# pca20020_sheet7_sound_and_light.net
KiCad netlist of a schematic drawn in Altium Designer
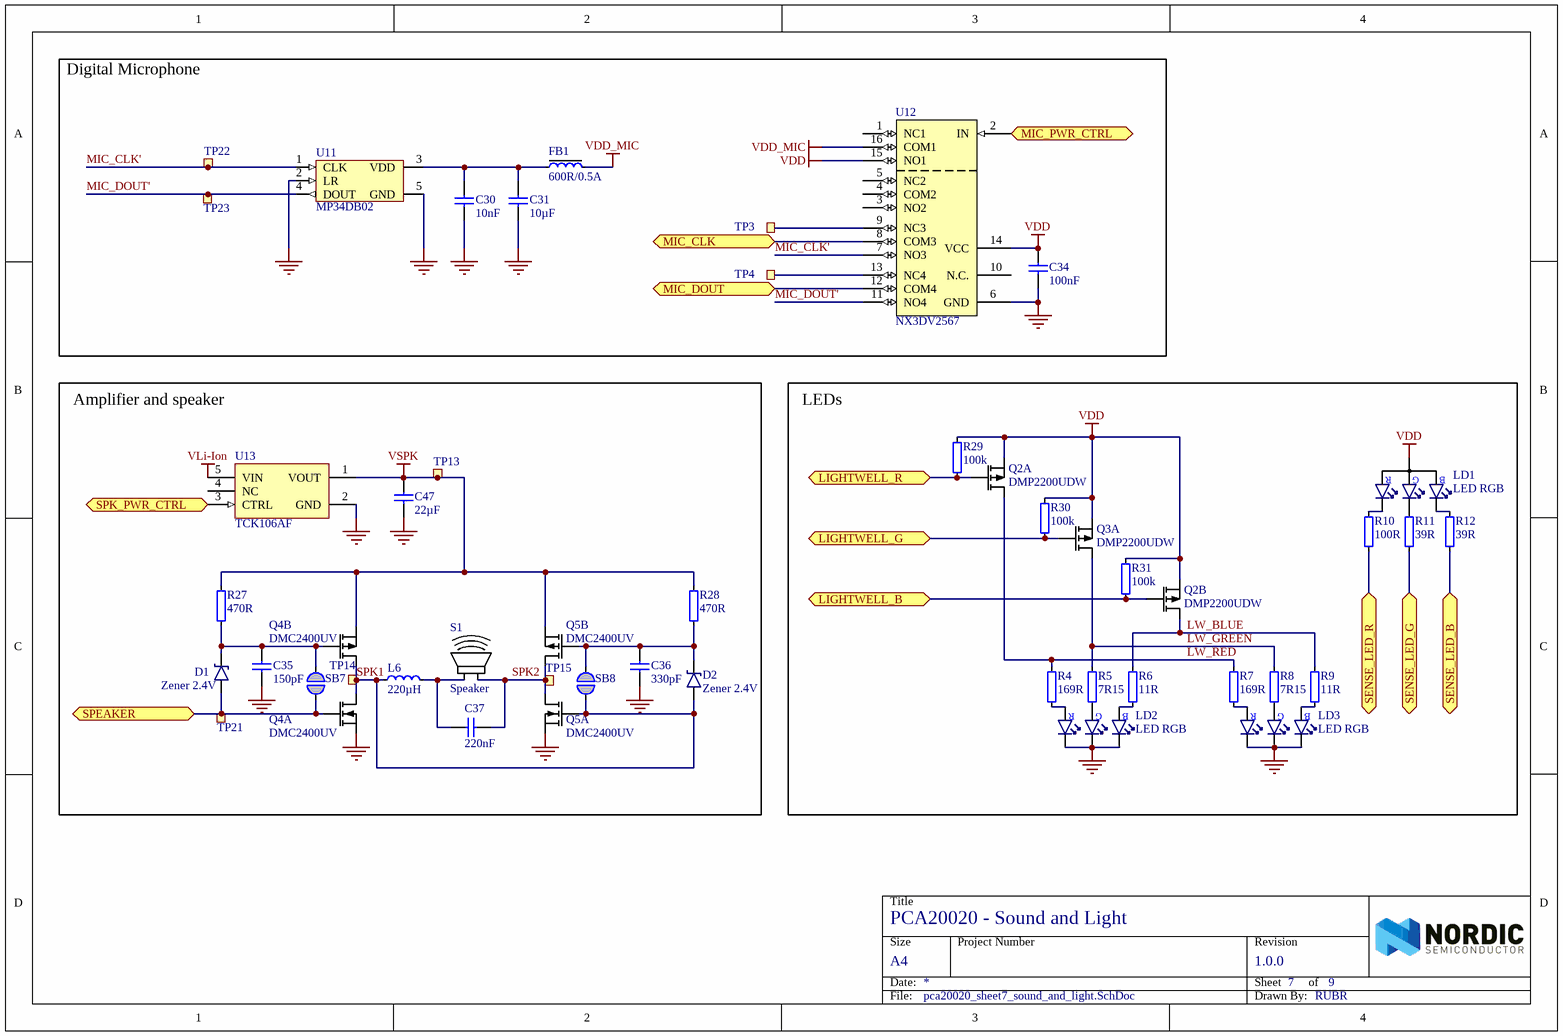
[diagram p0: pca20020_sheet7_sound_and_light.SchDoc]

(export (version "E")
  (design (tool "Eeschema 10.0.6"))
  (components
    (comp (ref "C30")
      (value "10nF")
      (footprint "CAPC1005X04L")
      (description "Capacitor, X7R, ±10%")
      (fields (field (name "PART NUMBER") "C0402-10n") (field (name "PUBLISHER") "Nordic Semiconductor"))
      (libsource (lib "Nordic Passive DB") (part "CAP"))
    )
    (comp (ref "C31")
      (value "10µF")
      (footprint "CAPC1608X06L")
      (description "Capacitor, X5R, ±20%")
      (fields (field (name "PART NUMBER") "C0603-10µ") (field (name "PUBLISHER") "Nordic Semiconductor"))
      (libsource (lib "Nordic Passive DB") (part "CAP"))
    )
    (comp (ref "C34")
      (value "100nF")
      (footprint "CAPC1005X04L")
      (description "Capacitor, X7R, ±10%")
      (fields (field (name "PART NUMBER") "C0402-100n") (field (name "PUBLISHER") "Nordic Semiconductor"))
      (libsource (lib "Nordic Passive DB") (part "CAP"))
    )
    (comp (ref "C35")
      (value "150pF")
      (footprint "CAPC1005X04L")
      (description "Capacitor, NP0, ±5%")
      (fields (field (name "PART NUMBER") "C0402-150p") (field (name "PUBLISHER") "Nordic Semiconductor"))
      (libsource (lib "Nordic Passive DB") (part "CAP"))
    )
    (comp (ref "C36")
      (value "330pF")
      (footprint "CAPC1005X04L")
      (description "Capacitor, NP0, ±5%")
      (fields (field (name "PART NUMBER") "C0402-330p") (field (name "PUBLISHER") "Nordic Semiconductor"))
      (libsource (lib "Nordic Passive DB") (part "CAP"))
    )
    (comp (ref "C37")
      (value "220nF")
      (footprint "CAPC1005X04L")
      (description "Capacitor, X7R, ±10%")
      (fields (field (name "PART NUMBER") "C0402-220n") (field (name "PUBLISHER") "Nordic Semiconductor"))
      (libsource (lib "Nordic Passive DB") (part "CAP"))
    )
    (comp (ref "C47")
      (value "22µF")
      (footprint "CAPC1608X06L")
      (description "CAP CER 22UF 6.3V 20% X5R 0603")
      (fields
        (field (name "PART NUMBER") "C0603-22µ-6.3V")
        (field (name "MANUFACTURER") "Samsung")
        (field (name "PUBLISHER") "Nordic Semiconductor")
      )
      (libsource (lib "Nordic Passive DB") (part "CAP"))
    )
    (comp (ref "D1")
      (value "Zener 2.4V")
      (footprint "SOD-523")
      (description "Diode, Zener, 2.4V, 0.3W")
      (fields
        (field (name "PART NUMBER") "BZT52C2V4T")
        (field (name "MANUFACTURER") "Diodes Incorporated")
        (field (name "PUBLISHER") "Nordic Semiconductor")
      )
      (libsource (lib "Nordic Discrete DB") (part "D{colon}ZENER"))
    )
    (comp (ref "D2")
      (value "Zener 2.4V")
      (footprint "SOD-523")
      (description "Diode, Zener, 2.4V, 0.3W")
      (fields
        (field (name "PART NUMBER") "BZT52C2V4T")
        (field (name "MANUFACTURER") "Diodes Incorporated")
        (field (name "PUBLISHER") "Nordic Semiconductor")
      )
      (libsource (lib "Nordic Discrete DB") (part "D{colon}ZENER"))
    )
    (comp (ref "FB1")
      (value "600R/0.5A")
      (footprint "INDC1608X06L")
      (description "Ferrite Bead, 600 Ohm @ 100MHz, 500mA, 380 mOhm Max")
      (fields
        (field (name "PART NUMBER") "FB0603-600R@100MHz-500mA")
        (field (name "MANUFACTURER") "Murata")
        (field (name "PUBLISHER") "Nordic Semiconductor")
      )
      (libsource (lib "Nordic Passive DB") (part "IND_F"))
    )
    (comp (ref "L6")
      (value "220µH")
      (footprint "INDP4040X25N")
      (description "Inductor, ±20%, 200mA, 2.76 Ohm")
      (fields
        (field (name "PART NUMBER") "L4040-220µ")
        (field (name "MANUFACTURER") "Bourns")
        (field (name "PUBLISHER") "Nordic Semiconductor")
      )
      (libsource (lib "Nordic Passive DB") (part "IND"))
    )
    (comp (ref "LD1")
      (value "LED RGB")
      (footprint "LED_RGB_0606")
      (description "RGB LED 1.60 mm x 1.60 mm SMD")
      (fields
        (field (name "PART NUMBER") "LTST-C19HE1WT")
        (field (name "MANUFACTURER") "Lite-On Inc")
        (field (name "PUBLISHER") "Nordic Semiconductor")
      )
      (libsource (lib "Nordic Discrete DB") (part "D{colon}LED_RGB"))
    )
    (comp (ref "LD2")
      (value "LED RGB")
      (footprint "MSL0104")
      (description "High brightness, side view RGB LED")
      (fields
        (field (name "PART NUMBER") "MSL0104RGBU1")
        (field (name "MANUFACTURER") "ROHM")
        (field (name "PUBLISHER") "Nordic Semiconductor")
      )
      (libsource (lib "Nordic Discrete DB") (part "D{colon}LED_RGB_MSL0104"))
    )
    (comp (ref "LD3")
      (value "LED RGB")
      (footprint "MSL0104")
      (description "High brightness, side view RGB LED")
      (fields
        (field (name "PART NUMBER") "MSL0104RGBU1")
        (field (name "MANUFACTURER") "ROHM")
        (field (name "PUBLISHER") "Nordic Semiconductor")
      )
      (libsource (lib "Nordic Discrete DB") (part "D{colon}LED_RGB_MSL0104"))
    )
    (comp (ref "Q2")
      (value "DMP2200UDW")
      (footprint "SOT-363")
      (description "Dual P Ch MOFET, 900mA, 260mOhm, 450mW")
      (fields
        (field (name "MANUFACTURER") "Diodes Incorporated")
        (field (name "PUBLISHER") "Nordic Semiconductor")
      )
      (libsource (lib "Nordic Discrete DB") (part "T{colon}FET-P-DUAL"))
    )
    (comp (ref "Q3")
      (value "DMP2200UDW")
      (footprint "SOT-363")
      (description "Dual P Ch MOFET, 900mA, 260mOhm, 450mW")
      (fields
        (field (name "MANUFACTURER") "Diodes Incorporated")
        (field (name "PUBLISHER") "Nordic Semiconductor")
      )
      (libsource (lib "Nordic Discrete DB") (part "T{colon}FET-P-DUAL"))
    )
    (comp (ref "Q4")
      (value "DMC2400UV")
      (footprint "SOTFL50P162X60-6N")
      (description "Dual N & P Ch MOFET, 1.03A/0.7A, 480mOhm, 450mW")
      (fields
        (field (name "MANUFACTURER") "Diodes Incorporated")
        (field (name "PUBLISHER") "Nordic Semiconductor")
      )
      (libsource (lib "Nordic Discrete DB") (part "T{colon}FET-N/P-DUAL"))
    )
    (comp (ref "Q5")
      (value "DMC2400UV")
      (footprint "SOTFL50P162X60-6N")
      (description "Dual N & P Ch MOFET, 1.03A/0.7A, 480mOhm, 450mW")
      (fields
        (field (name "MANUFACTURER") "Diodes Incorporated")
        (field (name "PUBLISHER") "Nordic Semiconductor")
      )
      (libsource (lib "Nordic Discrete DB") (part "T{colon}FET-N/P-DUAL"))
    )
    (comp (ref "R4")
      (value "169R")
      (footprint "RESC1005X04L")
      (description "Resistor, ±1%, 0.063W")
      (fields (field (name "PART NUMBER") "R0402-169") (field (name "PUBLISHER") "Nordic Semiconductor"))
      (libsource (lib "Nordic Passive DB") (part "RES_1"))
    )
    (comp (ref "R5")
      (value "7R15")
      (footprint "RESC1005X04L")
      (description "Resistor, ±1%, 0.063W")
      (fields (field (name "PART NUMBER") "R0402-7R15") (field (name "PUBLISHER") "Nordic Semiconductor"))
      (libsource (lib "Nordic Passive DB") (part "RES_1"))
    )
    (comp (ref "R6")
      (value "11R")
      (footprint "RESC1005X04L")
      (description "Resistor, ±1%, 0.063W")
      (fields (field (name "PART NUMBER") "R0402-11R") (field (name "PUBLISHER") "Nordic Semiconductor"))
      (libsource (lib "Nordic Passive DB") (part "RES_1"))
    )
    (comp (ref "R7")
      (value "169R")
      (footprint "RESC1005X04L")
      (description "Resistor, ±1%, 0.063W")
      (fields (field (name "PART NUMBER") "R0402-169") (field (name "PUBLISHER") "Nordic Semiconductor"))
      (libsource (lib "Nordic Passive DB") (part "RES_1"))
    )
    (comp (ref "R8")
      (value "7R15")
      (footprint "RESC1005X04L")
      (description "Resistor, ±1%, 0.063W")
      (fields (field (name "PART NUMBER") "R0402-7R15") (field (name "PUBLISHER") "Nordic Semiconductor"))
      (libsource (lib "Nordic Passive DB") (part "RES_1"))
    )
    (comp (ref "R9")
      (value "11R")
      (footprint "RESC1005X04L")
      (description "Resistor, ±1%, 0.063W")
      (fields (field (name "PART NUMBER") "R0402-11R") (field (name "PUBLISHER") "Nordic Semiconductor"))
      (libsource (lib "Nordic Passive DB") (part "RES_1"))
    )
    (comp (ref "R10")
      (value "100R")
      (footprint "RESC1005X04L")
      (description "Resistor, ±1%, 0.063W")
      (fields (field (name "PART NUMBER") "R0402-100") (field (name "PUBLISHER") "Nordic Semiconductor"))
      (libsource (lib "Nordic Passive DB") (part "RES_1"))
    )
    (comp (ref "R11")
      (value "39R")
      (footprint "RESC1005X04L")
      (description "Resistor, ±1%, 0.063W")
      (fields (field (name "PART NUMBER") "R0402-39R") (field (name "PUBLISHER") "Nordic Semiconductor"))
      (libsource (lib "Nordic Passive DB") (part "RES_1"))
    )
    (comp (ref "R12")
      (value "39R")
      (footprint "RESC1005X04L")
      (description "Resistor, ±1%, 0.063W")
      (fields (field (name "PART NUMBER") "R0402-39R") (field (name "PUBLISHER") "Nordic Semiconductor"))
      (libsource (lib "Nordic Passive DB") (part "RES_1"))
    )
    (comp (ref "R27")
      (value "470R")
      (footprint "RESC1005X04L")
      (description "Resistor, ±1%, 0.063W")
      (fields (field (name "PART NUMBER") "R0402-470") (field (name "PUBLISHER") "Nordic Semiconductor"))
      (libsource (lib "Nordic Passive DB") (part "RES_1"))
    )
    (comp (ref "R28")
      (value "470R")
      (footprint "RESC1005X04L")
      (description "Resistor, ±1%, 0.063W")
      (fields (field (name "PART NUMBER") "R0402-470") (field (name "PUBLISHER") "Nordic Semiconductor"))
      (libsource (lib "Nordic Passive DB") (part "RES_1"))
    )
    (comp (ref "R29")
      (value "100k")
      (footprint "RESC1005X04L")
      (description "Resistor, ±1%, 0.063W")
      (fields (field (name "PART NUMBER") "R0402-100k") (field (name "PUBLISHER") "Nordic Semiconductor"))
      (libsource (lib "Nordic Passive DB") (part "RES_1"))
    )
    (comp (ref "R30")
      (value "100k")
      (footprint "RESC1005X04L")
      (description "Resistor, ±1%, 0.063W")
      (fields (field (name "PART NUMBER") "R0402-100k") (field (name "PUBLISHER") "Nordic Semiconductor"))
      (libsource (lib "Nordic Passive DB") (part "RES_1"))
    )
    (comp (ref "R31")
      (value "100k")
      (footprint "RESC1005X04L")
      (description "Resistor, ±1%, 0.063W")
      (fields (field (name "PART NUMBER") "R0402-100k") (field (name "PUBLISHER") "Nordic Semiconductor"))
      (libsource (lib "Nordic Passive DB") (part "RES_1"))
    )
    (comp (ref "S1")
      (value "Speaker")
      (footprint "Speaker 15x11x3mm")
      (description "Speaker, SMD, 15.0mm x 11.0mm x 3.0mm, 0Hz-20kHz, 89dB, 8 ohm, 0.7W")
      (fields
        (field (name "PART NUMBER") "BMS1511F-11C-08H03P LF")
        (field (name "MANUFACTURER") "BeStar")
        (field (name "PUBLISHER") "Nordic Semiconductor")
      )
      (libsource (lib "Nordic Passive DB") (part "Speaker"))
    )
    (comp (ref "SB7")
      (value "Solderbridge")
      (footprint "Solderbridge")
      (fields (field (name "PUBLISHER") "Nordic Semiconductor"))
      (libsource (lib "Nordic Passive DB") (part "SOLDERBRIDGE"))
    )
    (comp (ref "SB8")
      (value "Solderbridge")
      (footprint "Solderbridge")
      (fields (field (name "PUBLISHER") "Nordic Semiconductor"))
      (libsource (lib "Nordic Passive DB") (part "SOLDERBRIDGE"))
    )
    (comp (ref "TP3")
      (value "TP")
      (footprint "TESTPAD-TH")
      (description "Testpoint, through hole")
      (fields (field (name "PART NUMBER") "Testpoint TH") (field (name "PUBLISHER") "Nordic Semiconductor"))
      (libsource (lib "") (part "TESTPAD_1"))
    )
    (comp (ref "TP4")
      (value "TP")
      (footprint "TESTPAD-TH")
      (description "Testpoint, through hole")
      (fields (field (name "PART NUMBER") "Testpoint TH") (field (name "PUBLISHER") "Nordic Semiconductor"))
      (libsource (lib "") (part "TESTPAD_1"))
    )
    (comp (ref "TP13")
      (value "Ø1.5mm,SMD")
      (footprint "TP_SMD_Ø1.5mm")
      (description "1.0mm circular SMD testpad")
      (fields
        (field (name "PART NUMBER") "TP_SMD_Ø1.5MM")
        (field (name "MANUFACTURER") "Nordic Semiconductor")
        (field (name "PUBLISHER") "Nordic Semiconductor")
      )
      (libsource (lib "") (part "TESTPAD_2"))
    )
    (comp (ref "TP14")
      (value "Ø1.5mm,SMD")
      (footprint "TP_SMD_Ø1.5mm")
      (description "1.0mm circular SMD testpad")
      (fields
        (field (name "PART NUMBER") "TP_SMD_Ø1.5MM")
        (field (name "MANUFACTURER") "Nordic Semiconductor")
        (field (name "PUBLISHER") "Nordic Semiconductor")
      )
      (libsource (lib "") (part "TESTPAD_1"))
    )
    (comp (ref "TP15")
      (value "Ø1.5mm,SMD")
      (footprint "TP_SMD_Ø1.5mm")
      (description "1.0mm circular SMD testpad")
      (fields
        (field (name "PART NUMBER") "TP_SMD_Ø1.5MM")
        (field (name "MANUFACTURER") "Nordic Semiconductor")
        (field (name "PUBLISHER") "Nordic Semiconductor")
      )
      (libsource (lib "Nordic Passive DB") (part "TESTPAD"))
    )
    (comp (ref "TP21")
      (value "Ø1.5mm,SMD")
      (footprint "TP_SMD_Ø1.5mm")
      (description "1.0mm circular SMD testpad")
      (fields
        (field (name "PART NUMBER") "TP_SMD_Ø1.5MM")
        (field (name "MANUFACTURER") "Nordic Semiconductor")
        (field (name "PUBLISHER") "Nordic Semiconductor")
      )
      (libsource (lib "") (part "TESTPAD_3"))
    )
    (comp (ref "TP22")
      (value "Ø1.5mm,SMD")
      (footprint "TP_SMD_Ø1.5mm")
      (description "1.0mm circular SMD testpad")
      (fields
        (field (name "PART NUMBER") "TP_SMD_Ø1.5MM")
        (field (name "MANUFACTURER") "Nordic Semiconductor")
        (field (name "PUBLISHER") "Nordic Semiconductor")
      )
      (libsource (lib "") (part "TESTPAD_2"))
    )
    (comp (ref "TP23")
      (value "Ø1.5mm,SMD")
      (footprint "TP_SMD_Ø1.5mm")
      (description "1.0mm circular SMD testpad")
      (fields
        (field (name "PART NUMBER") "TP_SMD_Ø1.5MM")
        (field (name "MANUFACTURER") "Nordic Semiconductor")
        (field (name "PUBLISHER") "Nordic Semiconductor")
      )
      (libsource (lib "") (part "TESTPAD_3"))
    )
    (comp (ref "U11")
      (value "MP34DB02")
      (footprint "RHLGA-4 (3x4x1mm)")
      (description "MEMS audio sensor omnidirectional digital microphone")
      (fields
        (field (name "MANUFACTURER") "STMicroelectronics")
        (field (name "2ND SOURCE PART NUMBER") "511-MP34DB02TR")
        (field (name "PUBLISHER") "Nordic Semiconductor")
      )
      (libsource (lib "Nordic Active DB") (part "DIG_MIC-5-pin"))
    )
    (comp (ref "U12")
      (value "NX3DV2567")
      (footprint "XQFN40P180X260X50-16N")
      (description "Low-ohmic four-pole double-throw analog switch")
      (fields
        (field (name "PART NUMBER") "NX3DV2567GU")
        (field (name "MANUFACTURER") "NXP Semiconductors")
        (field (name "PUBLISHER") "Nordic Semiconductor")
      )
      (libsource (lib "Nordic Active DB") (part "NX3DV2567"))
    )
    (comp (ref "U13")
      (value "TCK106AF")
      (footprint "SOT95P280X140-5N")
      (description "1.0 A Load Switch IC with Slew Rate Control Driver in Small Package")
      (fields
        (field (name "PART NUMBER") "TCK106AF,LF")
        (field (name "MANUFACTURER") "Toshiba")
        (field (name "PUBLISHER") "Nordic Semiconductor")
      )
      (libsource (lib "Nordic Active DB") (part "TCK10xAF"))
    )
  )
  (nets
    (net (code "1") (name "/LIGHTWELL_B") (class "Default")
      (node (ref "Q2") (pin "5") (pinfunction "G2_5") (pintype "passive"))
      (node (ref "R31") (pin "2") (pinfunction "2_2") (pintype "passive"))
    )
    (net (code "2") (name "/LIGHTWELL_G") (class "Default")
      (node (ref "Q3") (pin "2") (pinfunction "G1_2") (pintype "passive"))
      (node (ref "R30") (pin "2") (pinfunction "2_2") (pintype "passive"))
    )
    (net (code "3") (name "/LIGHTWELL_R") (class "Default")
      (node (ref "Q2") (pin "2") (pinfunction "G1_2") (pintype "passive"))
      (node (ref "R29") (pin "2") (pinfunction "2_2") (pintype "passive"))
    )
    (net (code "4") (name "/LW_BLUE") (class "Default")
      (node (ref "Q2") (pin "3") (pinfunction "D2_3") (pintype "passive"))
      (node (ref "R6") (pin "1") (pinfunction "1_1") (pintype "passive"))
      (node (ref "R9") (pin "1") (pinfunction "1_1") (pintype "passive"))
    )
    (net (code "5") (name "/LW_GREEN") (class "Default")
      (node (ref "Q3") (pin "6") (pinfunction "D1_6") (pintype "passive"))
      (node (ref "R5") (pin "1") (pinfunction "1_1") (pintype "passive"))
      (node (ref "R8") (pin "1") (pinfunction "1_1") (pintype "passive"))
    )
    (net (code "6") (name "/LW_RED") (class "Default")
      (node (ref "Q2") (pin "6") (pinfunction "D1_6") (pintype "passive"))
      (node (ref "R4") (pin "1") (pinfunction "1_1") (pintype "passive"))
      (node (ref "R7") (pin "1") (pinfunction "1_1") (pintype "passive"))
    )
    (net (code "7") (name "/MIC_CLK") (class "Default")
      (node (ref "U12") (pin "8") (pinfunction "COM3_8") (pintype "bidirectional"))
    )
    (net (code "8") (name "/MIC_CLK'") (class "Default")
      (node (ref "TP22") (pin "1") (pinfunction "1_1") (pintype "passive"))
      (node (ref "U11") (pin "1") (pinfunction "CLK_1") (pintype "input"))
      (node (ref "U12") (pin "7") (pinfunction "NO3_7") (pintype "bidirectional"))
    )
    (net (code "9") (name "/MIC_DOUT") (class "Default")
      (node (ref "U12") (pin "12") (pinfunction "COM4_12") (pintype "bidirectional"))
    )
    (net (code "10") (name "/MIC_DOUT'") (class "Default")
      (node (ref "TP23") (pin "1") (pinfunction "1_1") (pintype "passive"))
      (node (ref "U11") (pin "4") (pinfunction "DOUT_4") (pintype "output"))
      (node (ref "U12") (pin "11") (pinfunction "NO4_11") (pintype "bidirectional"))
    )
    (net (code "11") (name "/MIC_PWR_CTRL") (class "Default")
      (node (ref "U12") (pin "2") (pinfunction "IN_2") (pintype "input"))
    )
    (net (code "12") (name "/SENSE_LED_B") (class "Default")
      (node (ref "R12") (pin "1") (pinfunction "1_1") (pintype "passive"))
    )
    (net (code "13") (name "/SENSE_LED_G") (class "Default")
      (node (ref "R11") (pin "1") (pinfunction "1_1") (pintype "passive"))
    )
    (net (code "14") (name "/SENSE_LED_R") (class "Default")
      (node (ref "R10") (pin "1") (pinfunction "1_1") (pintype "passive"))
    )
    (net (code "15") (name "/SPEAKER") (class "Default")
      (node (ref "D1") (pin "1") (pinfunction "A_1") (pintype "passive"))
      (node (ref "Q4") (pin "2") (pinfunction "G1_2") (pintype "passive"))
      (node (ref "SB7") (pin "2") (pinfunction "1_2") (pintype "passive"))
      (node (ref "TP21") (pin "1") (pinfunction "1_1") (pintype "passive"))
    )
    (net (code "16") (name "/SPK1") (class "Default")
      (node (ref "D2") (pin "1") (pinfunction "A_1") (pintype "passive"))
      (node (ref "L6") (pin "1") (pinfunction "1_1") (pintype "passive"))
      (node (ref "Q4") (pin "3") (pinfunction "D2_3") (pintype "passive"))
      (node (ref "Q4") (pin "6") (pinfunction "D1_6") (pintype "passive"))
      (node (ref "Q5") (pin "2") (pinfunction "G1_2") (pintype "passive"))
      (node (ref "SB8") (pin "2") (pinfunction "1_2") (pintype "passive"))
      (node (ref "TP14") (pin "1") (pinfunction "1_1") (pintype "passive"))
    )
    (net (code "17") (name "/SPK2") (class "Default")
      (node (ref "C37") (pin "1") (pinfunction "1_1") (pintype "passive"))
      (node (ref "Q5") (pin "3") (pinfunction "D2_3") (pintype "passive"))
      (node (ref "Q5") (pin "6") (pinfunction "D1_6") (pintype "passive"))
      (node (ref "S1") (pin "2") (pinfunction "2_2") (pintype "passive"))
      (node (ref "TP15") (pin "1") (pinfunction "1_1") (pintype "passive"))
    )
    (net (code "18") (name "/SPK_PWR_CTRL") (class "Default")
      (node (ref "U13") (pin "3") (pinfunction "CTRL_3") (pintype "input"))
    )
    (net (code "19") (name "GND") (class "Default")
      (node (ref "C30") (pin "1") (pinfunction "1_1") (pintype "passive"))
      (node (ref "C31") (pin "1") (pinfunction "1_1") (pintype "passive"))
      (node (ref "C34") (pin "1") (pinfunction "1_1") (pintype "passive"))
      (node (ref "C35") (pin "1") (pinfunction "1_1") (pintype "passive"))
      (node (ref "C36") (pin "1") (pinfunction "1_1") (pintype "passive"))
      (node (ref "C47") (pin "1") (pinfunction "1_1") (pintype "passive"))
      (node (ref "LD2") (pin "3") (pinfunction "C_GREEN_3") (pintype "passive"))
      (node (ref "LD2") (pin "4") (pinfunction "C_RED_4") (pintype "passive"))
      (node (ref "LD2") (pin "5") (pinfunction "C_BLUE_5") (pintype "passive"))
      (node (ref "LD3") (pin "3") (pinfunction "C_GREEN_3") (pintype "passive"))
      (node (ref "LD3") (pin "4") (pinfunction "C_RED_4") (pintype "passive"))
      (node (ref "LD3") (pin "5") (pinfunction "C_BLUE_5") (pintype "passive"))
      (node (ref "Q4") (pin "1") (pinfunction "S1_1") (pintype "passive"))
      (node (ref "Q5") (pin "1") (pinfunction "S1_1") (pintype "passive"))
      (node (ref "U11") (pin "2") (pinfunction "LR_2") (pintype "input"))
      (node (ref "U11") (pin "5") (pinfunction "GND_5") (pintype "power_in"))
      (node (ref "U12") (pin "6") (pinfunction "GND_6") (pintype "power_in"))
      (node (ref "U13") (pin "2") (pinfunction "GND_2") (pintype "power_in"))
    )
    (net (code "20") (name "Net-(C37-Pad2)") (class "Default")
      (node (ref "C37") (pin "2") (pinfunction "2_2") (pintype "passive"))
      (node (ref "L6") (pin "2") (pinfunction "2_2") (pintype "passive"))
      (node (ref "S1") (pin "1") (pinfunction "1_1") (pintype "passive"))
    )
    (net (code "21") (name "Net-(D1-C)") (class "Default")
      (node (ref "C35") (pin "2") (pinfunction "2_2") (pintype "passive"))
      (node (ref "D1") (pin "3") (pinfunction "C_3") (pintype "passive"))
      (node (ref "Q4") (pin "5") (pinfunction "G2_5") (pintype "passive"))
      (node (ref "R27") (pin "2") (pinfunction "2_2") (pintype "passive"))
      (node (ref "SB7") (pin "1") (pinfunction "0_1") (pintype "passive"))
    )
    (net (code "22") (name "Net-(D2-C)") (class "Default")
      (node (ref "C36") (pin "2") (pinfunction "2_2") (pintype "passive"))
      (node (ref "D2") (pin "3") (pinfunction "C_3") (pintype "passive"))
      (node (ref "Q5") (pin "5") (pinfunction "G2_5") (pintype "passive"))
      (node (ref "R28") (pin "2") (pinfunction "2_2") (pintype "passive"))
      (node (ref "SB8") (pin "1") (pinfunction "0_1") (pintype "passive"))
    )
    (net (code "23") (name "Net-(LD1-C_BLUE)") (class "Default")
      (node (ref "LD1") (pin "3") (pinfunction "C_BLUE_3") (pintype "passive"))
      (node (ref "R12") (pin "2") (pinfunction "2_2") (pintype "passive"))
    )
    (net (code "24") (name "Net-(LD1-C_GREEN)") (class "Default")
      (node (ref "LD1") (pin "2") (pinfunction "C_GREEN_2") (pintype "passive"))
      (node (ref "R11") (pin "2") (pinfunction "2_2") (pintype "passive"))
    )
    (net (code "25") (name "Net-(LD1-C_RED)") (class "Default")
      (node (ref "LD1") (pin "1") (pinfunction "C_RED_1") (pintype "passive"))
      (node (ref "R10") (pin "2") (pinfunction "2_2") (pintype "passive"))
    )
    (net (code "26") (name "Net-(LD2-A_BLUE)") (class "Default")
      (node (ref "LD2") (pin "6") (pinfunction "A_BLUE_6") (pintype "passive"))
      (node (ref "R6") (pin "2") (pinfunction "2_2") (pintype "passive"))
    )
    (net (code "27") (name "Net-(LD2-A_GREEN)") (class "Default")
      (node (ref "LD2") (pin "2") (pinfunction "A_GREEN_2") (pintype "passive"))
      (node (ref "R5") (pin "2") (pinfunction "2_2") (pintype "passive"))
    )
    (net (code "28") (name "Net-(LD2-A_RED)") (class "Default")
      (node (ref "LD2") (pin "1") (pinfunction "A_RED_1") (pintype "passive"))
      (node (ref "R4") (pin "2") (pinfunction "2_2") (pintype "passive"))
    )
    (net (code "29") (name "Net-(LD3-A_BLUE)") (class "Default")
      (node (ref "LD3") (pin "6") (pinfunction "A_BLUE_6") (pintype "passive"))
      (node (ref "R9") (pin "2") (pinfunction "2_2") (pintype "passive"))
    )
    (net (code "30") (name "Net-(LD3-A_GREEN)") (class "Default")
      (node (ref "LD3") (pin "2") (pinfunction "A_GREEN_2") (pintype "passive"))
      (node (ref "R8") (pin "2") (pinfunction "2_2") (pintype "passive"))
    )
    (net (code "31") (name "Net-(LD3-A_RED)") (class "Default")
      (node (ref "LD3") (pin "1") (pinfunction "A_RED_1") (pintype "passive"))
      (node (ref "R7") (pin "2") (pinfunction "2_2") (pintype "passive"))
    )
    (net (code "32") (name "Net-(U11-VDD)") (class "Default")
      (node (ref "C30") (pin "2") (pinfunction "2_2") (pintype "passive"))
      (node (ref "C31") (pin "2") (pinfunction "2_2") (pintype "passive"))
      (node (ref "FB1") (pin "1") (pinfunction "1_1") (pintype "passive"))
      (node (ref "U11") (pin "3") (pinfunction "VDD_3") (pintype "power_in"))
    )
    (net (code "33") (name "Net-(U12-NC3)") (class "Default")
      (node (ref "TP3") (pin "1") (pinfunction "1_1") (pintype "passive"))
      (node (ref "U12") (pin "9") (pinfunction "NC3_9") (pintype "bidirectional"))
    )
    (net (code "34") (name "Net-(U12-NC4)") (class "Default")
      (node (ref "TP4") (pin "1") (pinfunction "1_1") (pintype "passive"))
      (node (ref "U12") (pin "13") (pinfunction "NC4_13") (pintype "bidirectional"))
    )
    (net (code "35") (name "VDD") (class "Default")
      (node (ref "C34") (pin "2") (pinfunction "2_2") (pintype "passive"))
      (node (ref "LD1") (pin "4") (pinfunction "A_4") (pintype "passive"))
      (node (ref "Q2") (pin "1") (pinfunction "S1_1") (pintype "passive"))
      (node (ref "Q2") (pin "4") (pinfunction "S2_4") (pintype "passive"))
      (node (ref "Q3") (pin "1") (pinfunction "S1_1") (pintype "passive"))
      (node (ref "R29") (pin "1") (pinfunction "1_1") (pintype "passive"))
      (node (ref "R30") (pin "1") (pinfunction "1_1") (pintype "passive"))
      (node (ref "R31") (pin "1") (pinfunction "1_1") (pintype "passive"))
      (node (ref "U12") (pin "14") (pinfunction "VCC_14") (pintype "power_in"))
      (node (ref "U12") (pin "15") (pinfunction "NO1_15") (pintype "bidirectional"))
    )
    (net (code "36") (name "VDD_MIC") (class "Default")
      (node (ref "FB1") (pin "2") (pinfunction "2_2") (pintype "passive"))
      (node (ref "U12") (pin "16") (pinfunction "COM1_16") (pintype "bidirectional"))
    )
    (net (code "37") (name "VLi-Ion") (class "Default")
      (node (ref "U13") (pin "5") (pinfunction "VIN_5") (pintype "power_in"))
    )
    (net (code "38") (name "VSPK") (class "Default")
      (node (ref "C47") (pin "2") (pinfunction "2_2") (pintype "passive"))
      (node (ref "Q4") (pin "4") (pinfunction "S2_4") (pintype "passive"))
      (node (ref "Q5") (pin "4") (pinfunction "S2_4") (pintype "passive"))
      (node (ref "R27") (pin "1") (pinfunction "1_1") (pintype "passive"))
      (node (ref "R28") (pin "1") (pinfunction "1_1") (pintype "passive"))
      (node (ref "TP13") (pin "1") (pinfunction "1_1") (pintype "passive"))
      (node (ref "U13") (pin "1") (pinfunction "VOUT_1") (pintype "power_in"))
    )
    (net (code "39") (name "unconnected-(U12-COM2-Pad4)") (class "Default")
      (node (ref "U12") (pin "4") (pinfunction "COM2_4") (pintype "bidirectional"))
    )
    (net (code "40") (name "unconnected-(U12-N.C.-Pad10)") (class "Default")
      (node (ref "U12") (pin "10") (pinfunction "N.C._10") (pintype "passive"))
    )
    (net (code "41") (name "unconnected-(U12-NC1-Pad1)") (class "Default")
      (node (ref "U12") (pin "1") (pinfunction "NC1_1") (pintype "bidirectional"))
    )
    (net (code "42") (name "unconnected-(U12-NC2-Pad5)") (class "Default")
      (node (ref "U12") (pin "5") (pinfunction "NC2_5") (pintype "bidirectional"))
    )
    (net (code "43") (name "unconnected-(U12-NO2-Pad3)") (class "Default")
      (node (ref "U12") (pin "3") (pinfunction "NO2_3") (pintype "bidirectional"))
    )
    (net (code "44") (name "unconnected-(U13-NC-Pad4)") (class "Default")
      (node (ref "U13") (pin "4") (pinfunction "NC_4") (pintype "passive"))
    )
  )
)
